# ATtiny_TIP120.net
KiCad netlist of a schematic drawn in EAGLE
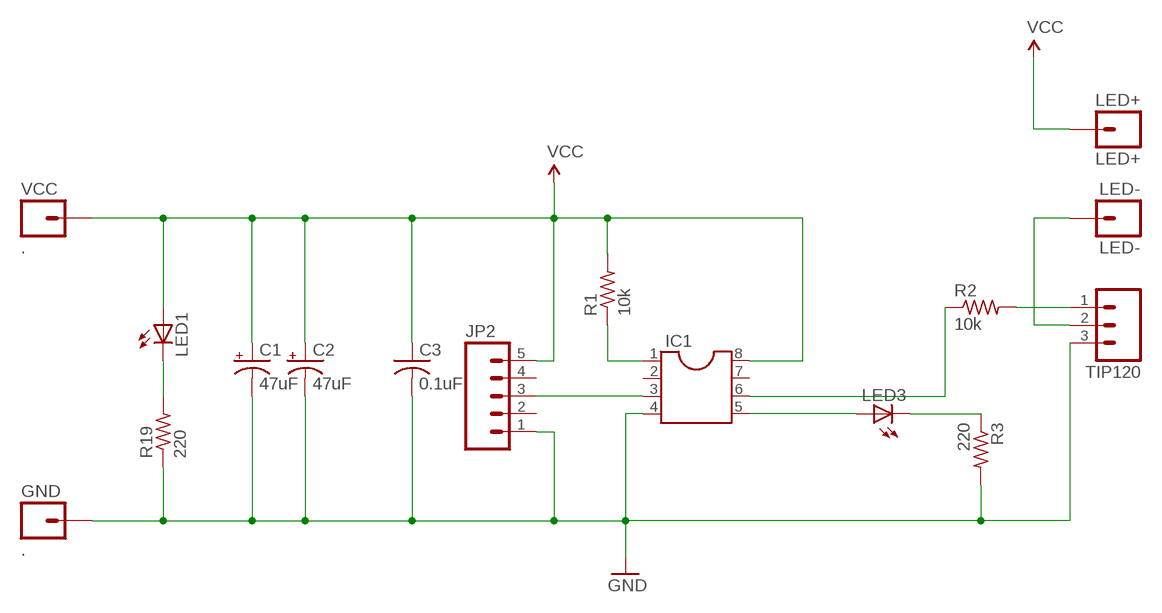
[diagram p0: schematic, sheet 1]

(export (version "E")
  (design (tool "Eeschema 10.0.6"))
  (components
    (comp (ref "C1")
      (value "47uF")
      (footprint "eagle-import:CPOL-RADIAL-1000UF-25V")
      (libsource (lib "eagle-import") (part "CAP_POLPTH4"))
    )
    (comp (ref "C2")
      (value "47uF")
      (footprint "eagle-import:CPOL-RADIAL-1000UF-25V")
      (libsource (lib "eagle-import") (part "CAP_POLPTH4"))
    )
    (comp (ref "C3")
      (value "0.1uF")
      (footprint "eagle-import:C025-025X050")
      (libsource (lib "eagle-import") (part "C-US025-025X050"))
    )
    (comp (ref "GND")
      (value ".")
      (footprint "eagle-import:1X01_OFFSET")
      (libsource (lib "eagle-import") (part "M01OFFSET"))
    )
    (comp (ref "IC1")
      (value "DIL8S")
      (footprint "eagle-import:SOCKET-08")
      (libsource (lib "eagle-import") (part "DIL8S"))
    )
    (comp (ref "JP2")
      (value "M05LOCK_LONGPADS")
      (footprint "eagle-import:1X05_LOCK_LONGPADS")
      (libsource (lib "eagle-import") (part "M05LOCK_LONGPADS"))
    )
    (comp (ref "LED+")
      (value "LED+")
      (footprint "eagle-import:1X01_OFFSET")
      (libsource (lib "eagle-import") (part "M01OFFSET"))
    )
    (comp (ref "LED-")
      (value "LED-")
      (footprint "eagle-import:1X01_OFFSET")
      (libsource (lib "eagle-import") (part "M01OFFSET"))
    )
    (comp (ref "LED1")
      (value "LED5MM")
      (footprint "eagle-import:LED5MM")
      (libsource (lib "eagle-import") (part "LED5MM"))
    )
    (comp (ref "LED3")
      (value "LED5MM")
      (footprint "eagle-import:LED5MM")
      (libsource (lib "eagle-import") (part "LED5MM"))
    )
    (comp (ref "R1")
      (value "10k")
      (footprint "eagle-import:0207_7")
      (libsource (lib "eagle-import") (part "R-US_0207/7"))
    )
    (comp (ref "R2")
      (value "10k")
      (footprint "eagle-import:0207_7")
      (libsource (lib "eagle-import") (part "R-US_0207/7"))
    )
    (comp (ref "R3")
      (value "220")
      (footprint "eagle-import:0207_7")
      (libsource (lib "eagle-import") (part "R-US_0207/7"))
    )
    (comp (ref "R19")
      (value "220")
      (footprint "eagle-import:0207_7")
      (libsource (lib "eagle-import") (part "R-US_0207/7"))
    )
    (comp (ref "TIP120")
      (value "M03LOCK_LONGPADS")
      (footprint "eagle-import:1X03_LOCK_LONGPADS")
      (libsource (lib "eagle-import") (part "M03LOCK_LONGPADS"))
    )
    (comp (ref "VCC")
      (value ".")
      (footprint "eagle-import:1X01_OFFSET")
      (libsource (lib "eagle-import") (part "M01OFFSET"))
    )
  )
  (nets
    (net (code "1") (name "GND") (class "Default")
      (node (ref "C1") (pin "2") (pinfunction "-_2") (pintype "passive"))
      (node (ref "C2") (pin "2") (pinfunction "-_2") (pintype "passive"))
      (node (ref "C3") (pin "2") (pinfunction "2_2") (pintype "passive"))
      (node (ref "GND") (pin "1") (pinfunction "1_1") (pintype "passive"))
      (node (ref "IC1") (pin "4") (pinfunction "4_4") (pintype "passive"))
      (node (ref "JP2") (pin "1") (pinfunction "1_1") (pintype "passive"))
      (node (ref "R19") (pin "1") (pinfunction "1_1") (pintype "passive"))
      (node (ref "R3") (pin "2") (pinfunction "2_2") (pintype "passive"))
      (node (ref "TIP120") (pin "3") (pinfunction "3_3") (pintype "passive"))
    )
    (net (code "2") (name "Net-(IC1-Pad1)") (class "Default")
      (node (ref "IC1") (pin "1") (pinfunction "1_1") (pintype "passive"))
      (node (ref "R1") (pin "1") (pinfunction "1_1") (pintype "passive"))
    )
    (net (code "3") (name "Net-(IC1-Pad3)") (class "Default")
      (node (ref "IC1") (pin "3") (pinfunction "3_3") (pintype "passive"))
      (node (ref "JP2") (pin "3") (pinfunction "3_3") (pintype "passive"))
    )
    (net (code "4") (name "Net-(IC1-Pad5)") (class "Default")
      (node (ref "IC1") (pin "5") (pinfunction "5_5") (pintype "passive"))
      (node (ref "LED3") (pin "A") (pinfunction "A_A") (pintype "passive"))
    )
    (net (code "5") (name "Net-(IC1-Pad6)") (class "Default")
      (node (ref "IC1") (pin "6") (pinfunction "6_6") (pintype "passive"))
      (node (ref "R2") (pin "1") (pinfunction "1_1") (pintype "passive"))
    )
    (net (code "6") (name "Net-(LED--Pad1)") (class "Default")
      (node (ref "LED-") (pin "1") (pinfunction "1_1") (pintype "passive"))
      (node (ref "TIP120") (pin "2") (pinfunction "2_2") (pintype "passive"))
    )
    (net (code "7") (name "Net-(LED1-C)") (class "Default")
      (node (ref "LED1") (pin "K") (pinfunction "C_K") (pintype "passive"))
      (node (ref "R19") (pin "2") (pinfunction "2_2") (pintype "passive"))
    )
    (net (code "8") (name "Net-(LED3-C)") (class "Default")
      (node (ref "LED3") (pin "K") (pinfunction "C_K") (pintype "passive"))
      (node (ref "R3") (pin "1") (pinfunction "1_1") (pintype "passive"))
    )
    (net (code "9") (name "Net-(R2-Pad2)") (class "Default")
      (node (ref "R2") (pin "2") (pinfunction "2_2") (pintype "passive"))
      (node (ref "TIP120") (pin "1") (pinfunction "1_1") (pintype "passive"))
    )
    (net (code "10") (name "VCC") (class "Default")
      (node (ref "C1") (pin "1") (pinfunction "+_1") (pintype "passive"))
      (node (ref "C2") (pin "1") (pinfunction "+_1") (pintype "passive"))
      (node (ref "C3") (pin "1") (pinfunction "1_1") (pintype "passive"))
      (node (ref "IC1") (pin "8") (pinfunction "8_8") (pintype "passive"))
      (node (ref "JP2") (pin "5") (pinfunction "5_5") (pintype "passive"))
      (node (ref "LED+") (pin "1") (pinfunction "1_1") (pintype "passive"))
      (node (ref "LED1") (pin "A") (pinfunction "A_A") (pintype "passive"))
      (node (ref "R1") (pin "2") (pinfunction "2_2") (pintype "passive"))
      (node (ref "VCC") (pin "1") (pinfunction "1_1") (pintype "passive"))
    )
    (net (code "11") (name "unconnected-(IC1-Pad2)") (class "Default")
      (node (ref "IC1") (pin "2") (pinfunction "2_2") (pintype "passive"))
    )
    (net (code "12") (name "unconnected-(IC1-Pad7)") (class "Default")
      (node (ref "IC1") (pin "7") (pinfunction "7_7") (pintype "passive"))
    )
    (net (code "13") (name "unconnected-(JP2-Pad2)") (class "Default")
      (node (ref "JP2") (pin "2") (pinfunction "2_2") (pintype "passive"))
    )
    (net (code "14") (name "unconnected-(JP2-Pad4)") (class "Default")
      (node (ref "JP2") (pin "4") (pinfunction "4_4") (pintype "passive"))
    )
  )
)
